# MCU.net
KiCad netlist of a schematic drawn in Altium Designer
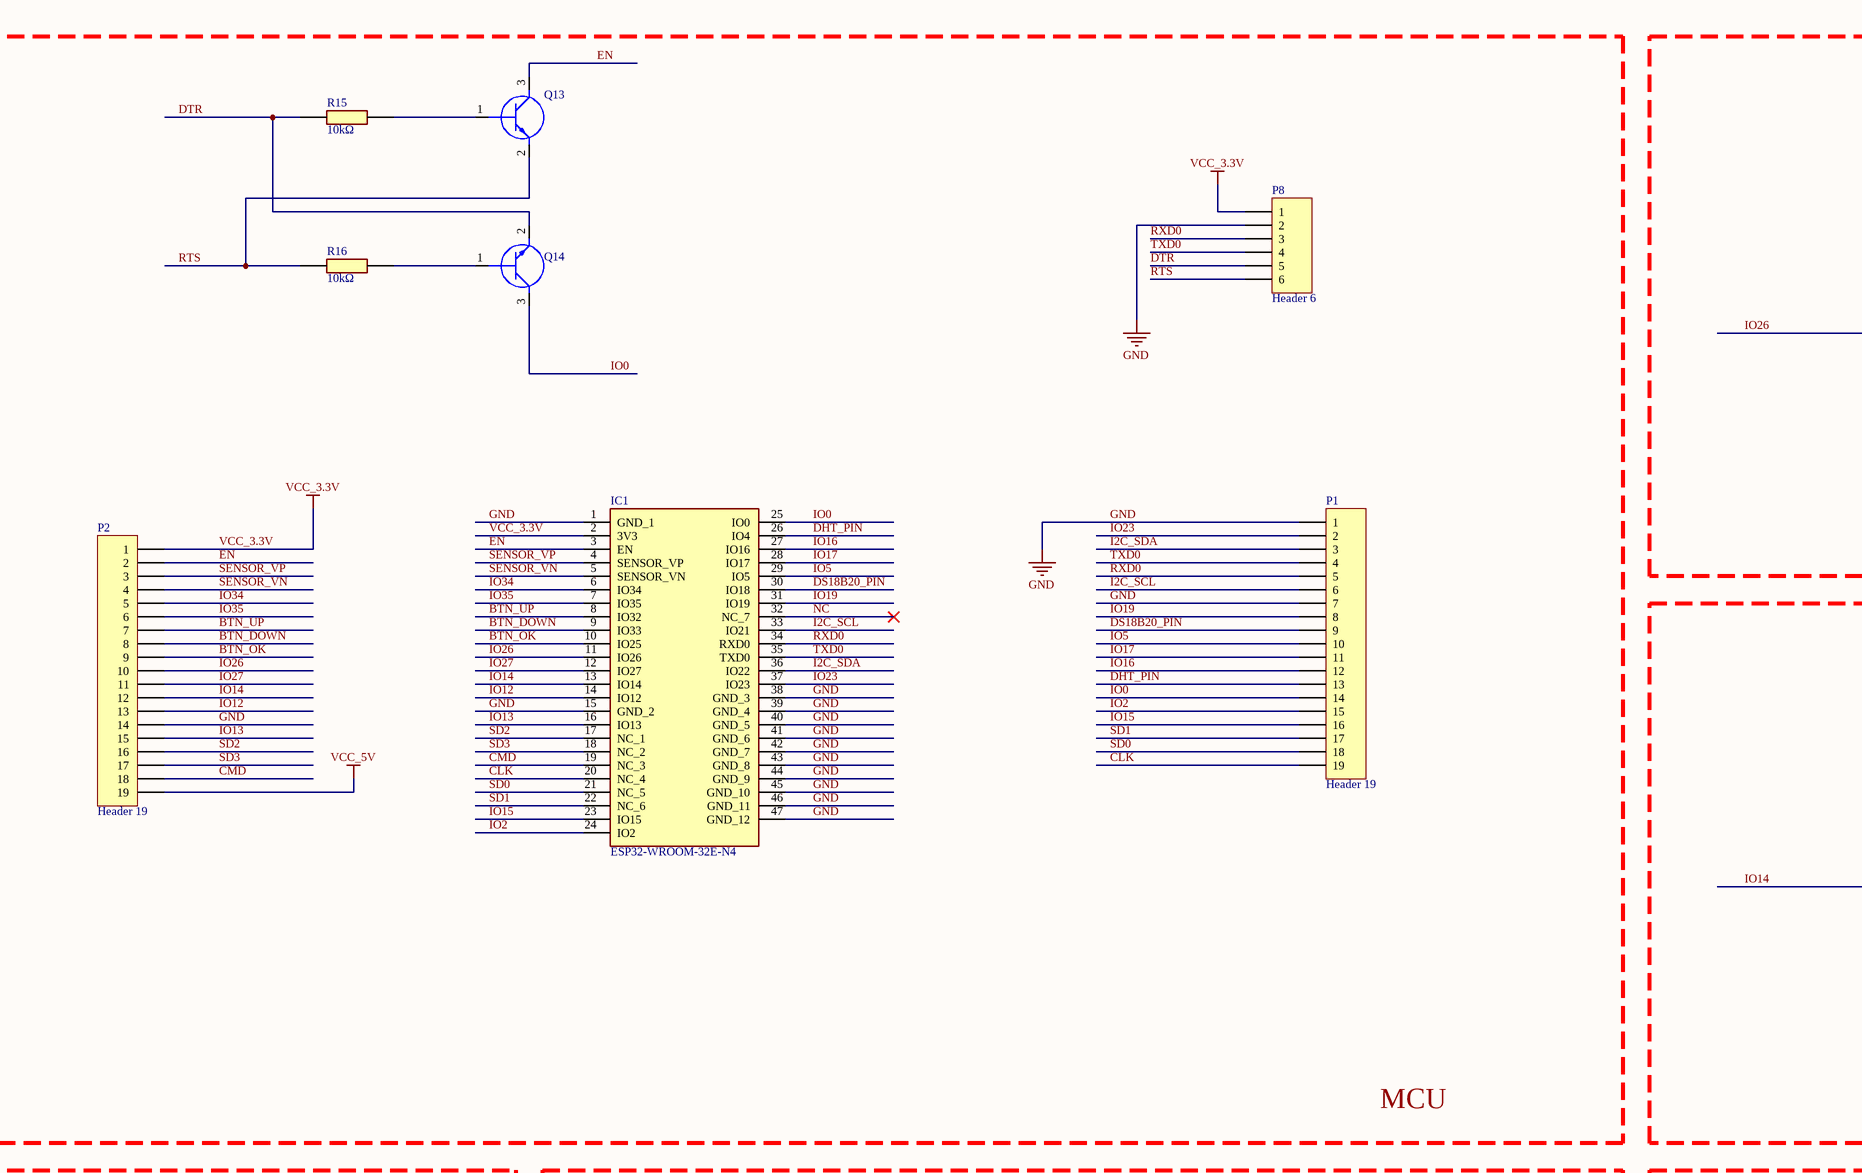
[diagram p0: MCU.SchDoc, top left]
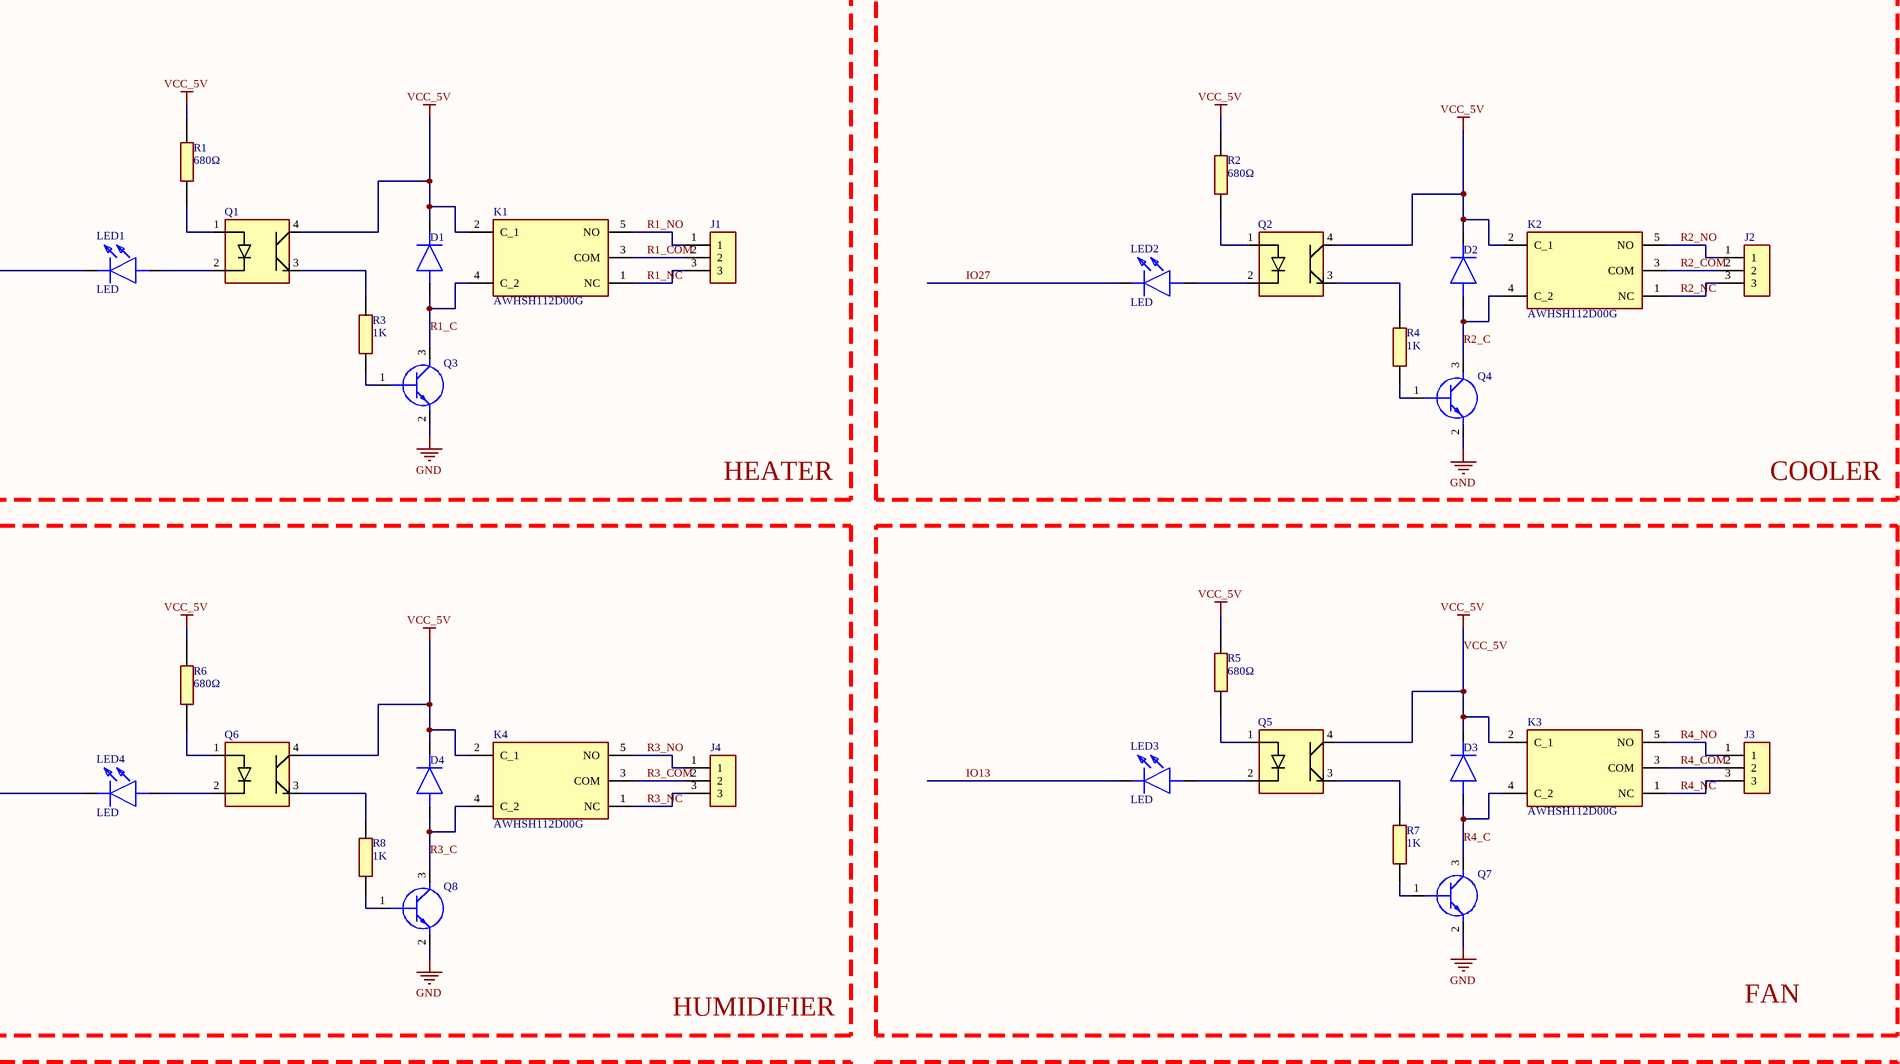
[diagram p1: MCU.SchDoc, top right]
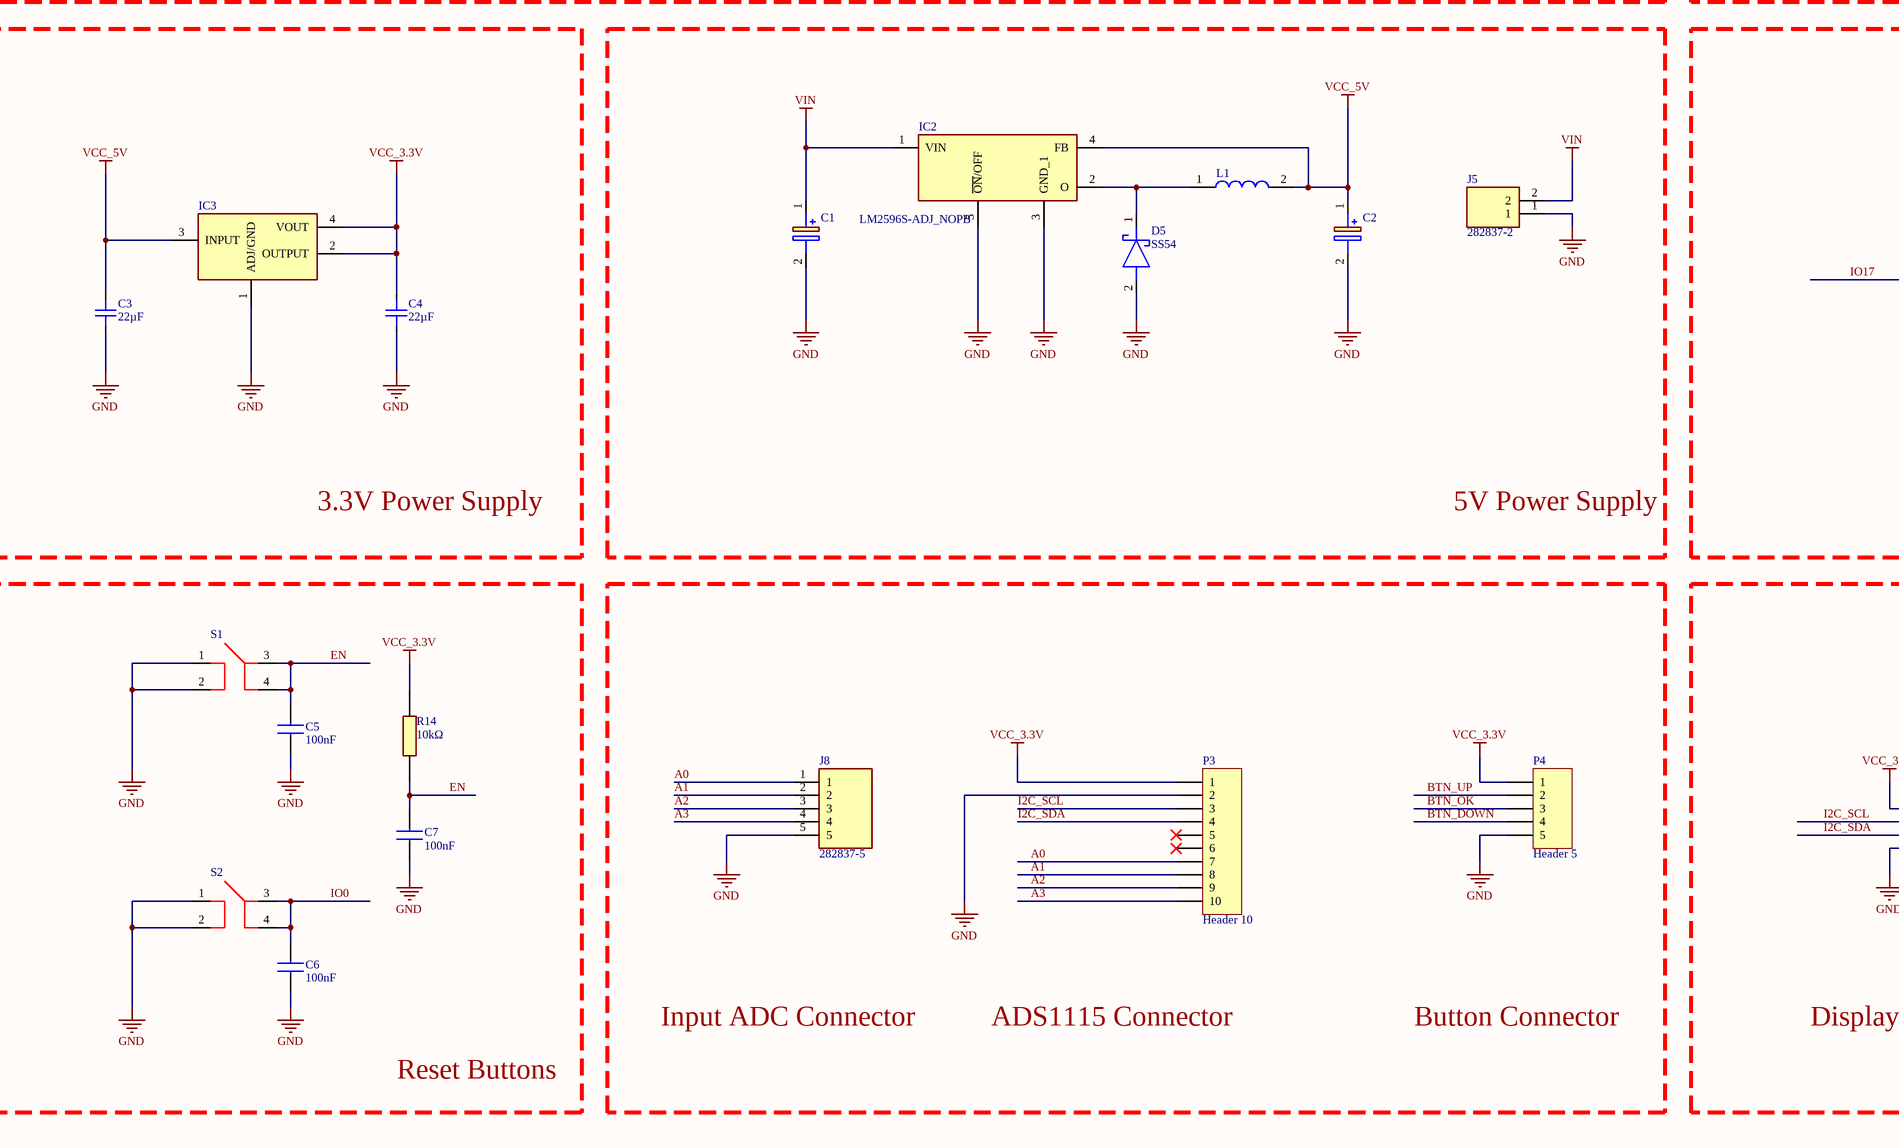
[diagram p2: MCU.SchDoc, bottom left]
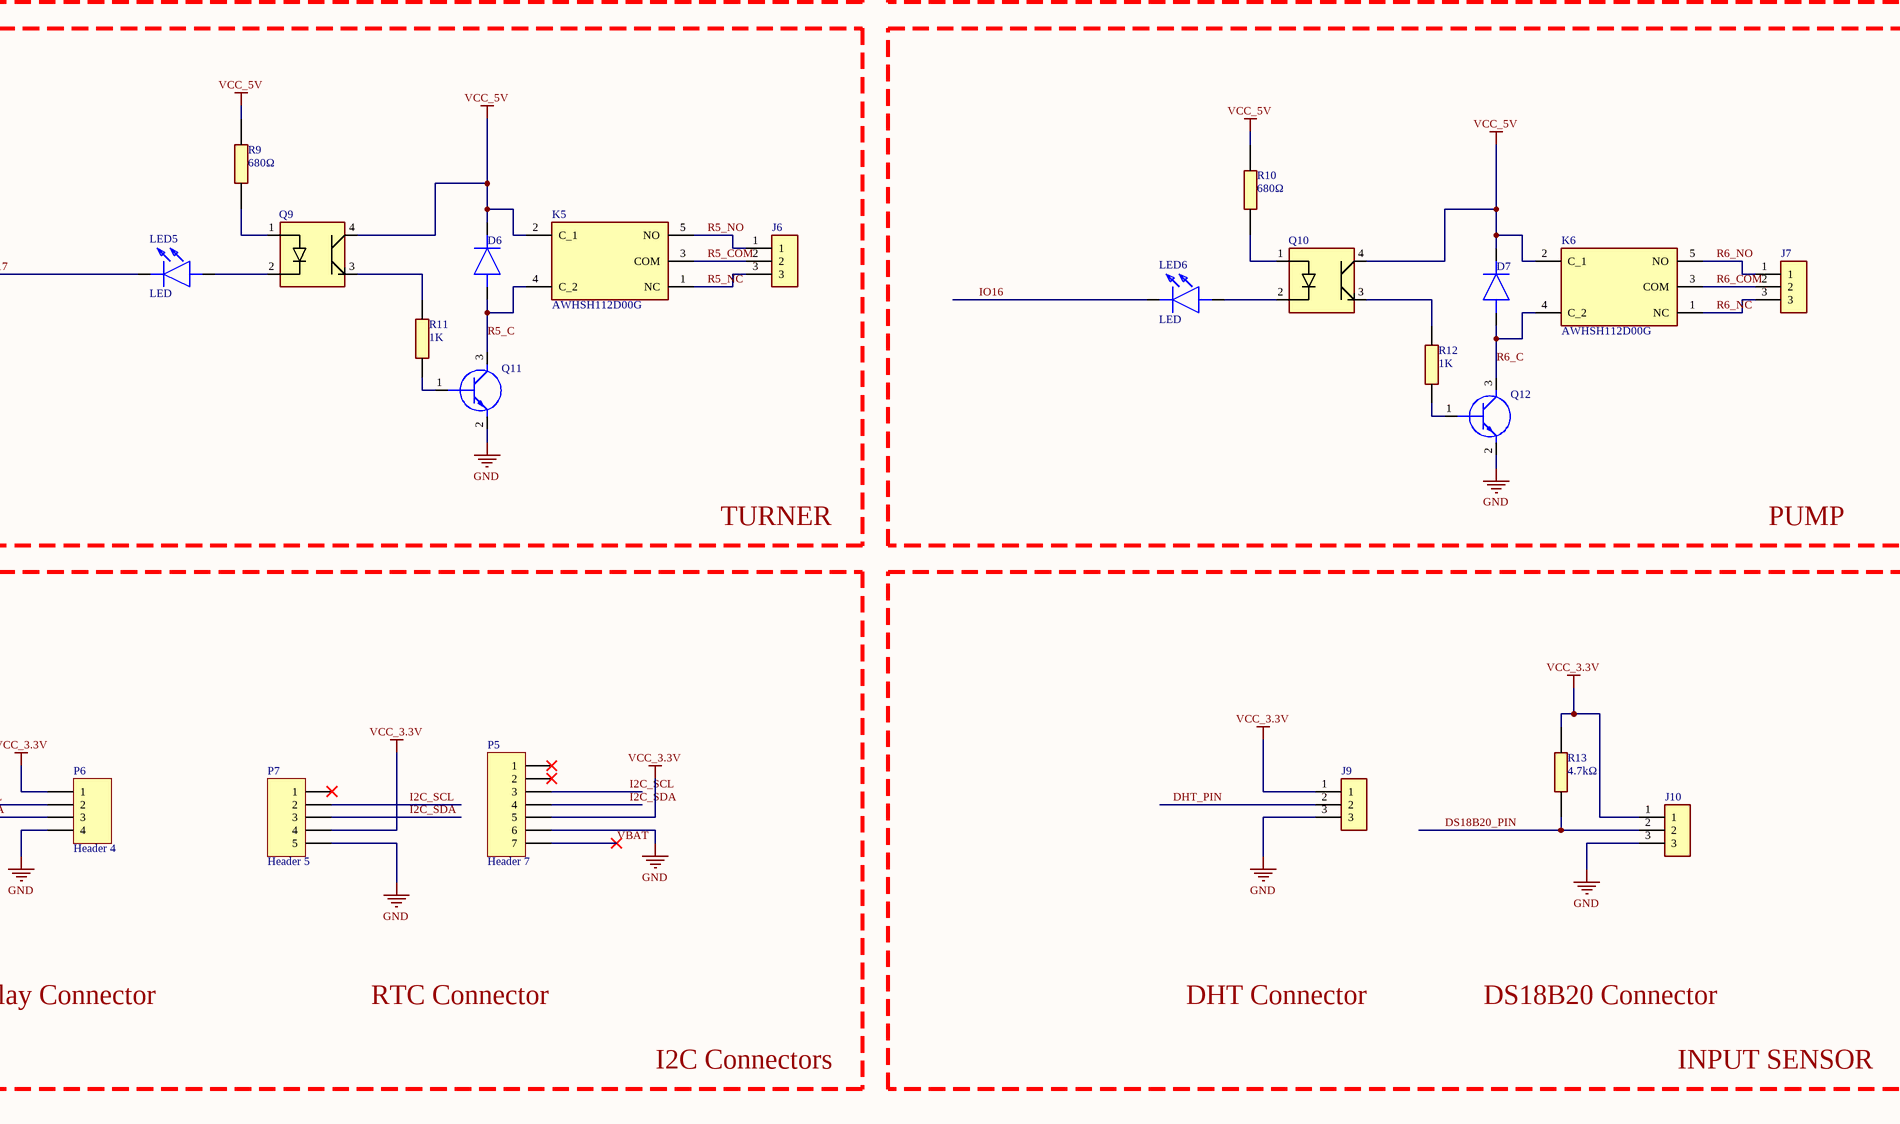
[diagram p3: MCU.SchDoc, bottom right]

(export (version "E")
  (design (tool "Eeschema 10.0.6"))
  (components
    (comp (ref "C1")
      (value "865060453007")
      (footprint "eggubator:CAPAE830X1050N")
      (description "Capacitor Polarised")
      (fields (field (name "MOUSER PART NUMBER") "710-865060453007"))
      (libsource (lib "*") (part "865060453007"))
    )
    (comp (ref "C2")
      (value "865060453007")
      (footprint "eggubator:CAPAE830X1050N")
      (description "Capacitor Polarised")
      (fields (field (name "MOUSER PART NUMBER") "710-865060453007"))
      (libsource (lib "*") (part "865060453007"))
    )
    (comp (ref "C3")
      (value "22µF")
      (footprint "C0805")
      (description "16V 22uF X5R ±20% 0805 Multilayer Ceramic Capacitors MLCC - SMD/SMT ROHS")
      (fields
        (field (name "MANUFACTURER") "Yageo Group")
        (field (name "MANUFACTURER PART NUMBER") "CC0805MKX5R7BB226")
      )
      (libsource (lib "eggubator") (part "CC0805MKX5R7BB226"))
    )
    (comp (ref "C4")
      (value "22µF")
      (footprint "C0805")
      (description "16V 22uF X5R ±20% 0805 Multilayer Ceramic Capacitors MLCC - SMD/SMT ROHS")
      (fields
        (field (name "MANUFACTURER") "Yageo Group")
        (field (name "MANUFACTURER PART NUMBER") "CC0805MKX5R7BB226")
      )
      (libsource (lib "eggubator") (part "CC0805MKX5R7BB226"))
    )
    (comp (ref "C5")
      (value "100nF")
      (footprint "C0805")
      (description "50V 100nF X7R ±10% 0805 Multilayer Ceramic Capacitors MLCC - SMD/SMT ROHS")
      (fields
        (field (name "MANUFACTURER") "Yageo Group")
        (field (name "MANUFACTURER PART NUMBER") "C0805C104K5RACTU")
      )
      (libsource (lib "eggubator") (part "C0805C104K5RACTU"))
    )
    (comp (ref "C6")
      (value "100nF")
      (footprint "C0805")
      (description "50V 100nF X7R ±10% 0805 Multilayer Ceramic Capacitors MLCC - SMD/SMT ROHS")
      (fields
        (field (name "MANUFACTURER") "Yageo Group")
        (field (name "MANUFACTURER PART NUMBER") "C0805C104K5RACTU")
      )
      (libsource (lib "eggubator") (part "C0805C104K5RACTU"))
    )
    (comp (ref "C7")
      (value "100nF")
      (footprint "C0805")
      (description "50V 100nF X7R ±10% 0805 Multilayer Ceramic Capacitors MLCC - SMD/SMT ROHS")
      (fields
        (field (name "MANUFACTURER") "Yageo Group")
        (field (name "MANUFACTURER PART NUMBER") "C0805C104K5RACTU")
      )
      (libsource (lib "eggubator") (part "C0805C104K5RACTU"))
    )
    (comp (ref "D1")
      (value "1N4007FLTR")
      (footprint "eggubator:SODFL3718X140N")
      (description "Diode")
      (libsource (lib "eggubator") (part "1N4007FLTR"))
    )
    (comp (ref "D2")
      (value "1N4007FLTR")
      (footprint "eggubator:SODFL3718X140N")
      (description "Diode")
      (libsource (lib "eggubator") (part "1N4007FLTR"))
    )
    (comp (ref "D3")
      (value "1N4007FLTR")
      (footprint "eggubator:SODFL3718X140N")
      (description "Diode")
      (libsource (lib "eggubator") (part "1N4007FLTR"))
    )
    (comp (ref "D4")
      (value "1N4007FLTR")
      (footprint "eggubator:SODFL3718X140N")
      (description "Diode")
      (libsource (lib "eggubator") (part "1N4007FLTR"))
    )
    (comp (ref "D5")
      (value "SS54")
      (footprint "eggubator:DIOM5026X262N")
      (description "Schottky Diode")
      (libsource (lib "*") (part "SS54"))
    )
    (comp (ref "D6")
      (value "1N4007FLTR")
      (footprint "eggubator:SODFL3718X140N")
      (description "Diode")
      (libsource (lib "eggubator") (part "1N4007FLTR"))
    )
    (comp (ref "D7")
      (value "1N4007FLTR")
      (footprint "eggubator:SODFL3718X140N")
      (description "Diode")
      (libsource (lib "eggubator") (part "1N4007FLTR"))
    )
    (comp (ref "IC1")
      (value "ESP32-WROOM-32E-N4")
      (footprint "eggubator:ESP32WROOM32EN4")
      (description "Integrated Circuit")
      (fields (field (name "MOUSER PART NUMBER") "356-ESP32WRM32E132PH"))
      (libsource (lib "*") (part "ESP32-WROOM-32E-N4"))
    )
    (comp (ref "IC2")
      (value "LM2596S-ADJ_NOPB")
      (footprint "eggubator:LM2596SXADJ")
      (description "Integrated Circuit")
      (fields
        (field (name "MANUFACTURER_PART_NUMBER") "LM2596S-ADJ/NOPB")
        (field (name "MOUSER PART NUMBER") "926-LM2596S-ADJ/NOPB")
      )
      (libsource (lib "eggubator") (part "LM2596S-ADJ_NOPB"))
    )
    (comp (ref "IC3")
      (value "LM1117IMPX3.3_NOPB")
      (footprint "eggubator:SOT230P700X180-4N")
      (description "Integrated Circuit")
      (fields (field (name "MANUFACTURER_PART_NUMBER") "LM1117IMPX3.3/NOPB"))
      (libsource (lib "eggubator") (part "LM1117IMPX3.3_NOPB"))
    )
    (comp (ref "J1")
      (value "691137710003")
      (footprint "eggubator:691137710003")
      (description "Connector")
      (fields (field (name "MOUSER PART NUMBER") "710-691137710003"))
      (libsource (lib "eggubator") (part "691137710003"))
    )
    (comp (ref "J2")
      (value "691137710003")
      (footprint "eggubator:691137710003")
      (description "Connector")
      (fields (field (name "MOUSER PART NUMBER") "710-691137710003"))
      (libsource (lib "eggubator") (part "691137710003"))
    )
    (comp (ref "J3")
      (value "691137710003")
      (footprint "eggubator:691137710003")
      (description "Connector")
      (fields (field (name "MOUSER PART NUMBER") "710-691137710003"))
      (libsource (lib "eggubator") (part "691137710003"))
    )
    (comp (ref "J4")
      (value "691137710003")
      (footprint "eggubator:691137710003")
      (description "Connector")
      (fields (field (name "MOUSER PART NUMBER") "710-691137710003"))
      (libsource (lib "eggubator") (part "691137710003"))
    )
    (comp (ref "J5")
      (value "282837-2")
      (footprint "eggubator:2828372")
      (description "Connector")
      (fields (field (name "MOUSER PART NUMBER") "571-2828372"))
      (libsource (lib "*") (part "282837-2"))
    )
    (comp (ref "J6")
      (value "691137710003")
      (footprint "eggubator:691137710003")
      (description "Connector")
      (fields (field (name "MOUSER PART NUMBER") "710-691137710003"))
      (libsource (lib "eggubator") (part "691137710003"))
    )
    (comp (ref "J7")
      (value "691137710003")
      (footprint "eggubator:691137710003")
      (description "Connector")
      (fields (field (name "MOUSER PART NUMBER") "710-691137710003"))
      (libsource (lib "eggubator") (part "691137710003"))
    )
    (comp (ref "J8")
      (value "282837-5")
      (footprint "eggubator:2828375")
      (description "Connector")
      (fields (field (name "MOUSER PART NUMBER") "571-2828375"))
      (libsource (lib "*") (part "282837-5"))
    )
    (comp (ref "J9")
      (value "691137710003")
      (footprint "eggubator:691137710003")
      (description "Connector")
      (fields (field (name "MOUSER PART NUMBER") "710-691137710003"))
      (libsource (lib "eggubator") (part "691137710003"))
    )
    (comp (ref "J10")
      (value "691137710003")
      (footprint "eggubator:691137710003")
      (description "Connector")
      (fields (field (name "MOUSER PART NUMBER") "710-691137710003"))
      (libsource (lib "eggubator") (part "691137710003"))
    )
    (comp (ref "K1")
      (value "AWHSH112D00G")
      (footprint "eggubator:AWHSH112D00G")
      (description "Relay or Contactor")
      (fields (field (name "MOUSER PART NUMBER") "523-AWHSH112D00G"))
      (libsource (lib "eggubator") (part "AWHSH112D00G"))
    )
    (comp (ref "K2")
      (value "AWHSH112D00G")
      (footprint "eggubator:AWHSH112D00G")
      (description "Relay or Contactor")
      (fields (field (name "MOUSER PART NUMBER") "523-AWHSH112D00G"))
      (libsource (lib "eggubator") (part "AWHSH112D00G"))
    )
    (comp (ref "K3")
      (value "AWHSH112D00G")
      (footprint "eggubator:AWHSH112D00G")
      (description "Relay or Contactor")
      (fields (field (name "MOUSER PART NUMBER") "523-AWHSH112D00G"))
      (libsource (lib "eggubator") (part "AWHSH112D00G"))
    )
    (comp (ref "K4")
      (value "AWHSH112D00G")
      (footprint "eggubator:AWHSH112D00G")
      (description "Relay or Contactor")
      (fields (field (name "MOUSER PART NUMBER") "523-AWHSH112D00G"))
      (libsource (lib "eggubator") (part "AWHSH112D00G"))
    )
    (comp (ref "K5")
      (value "AWHSH112D00G")
      (footprint "eggubator:AWHSH112D00G")
      (description "Relay or Contactor")
      (fields (field (name "MOUSER PART NUMBER") "523-AWHSH112D00G"))
      (libsource (lib "eggubator") (part "AWHSH112D00G"))
    )
    (comp (ref "K6")
      (value "AWHSH112D00G")
      (footprint "eggubator:AWHSH112D00G")
      (description "Relay or Contactor")
      (fields (field (name "MOUSER PART NUMBER") "523-AWHSH112D00G"))
      (libsource (lib "eggubator") (part "AWHSH112D00G"))
    )
    (comp (ref "L1")
      (value "CDRH104RNP-331NC")
      (footprint "eggubator:CDRH104RNP331NC")
      (description "Inductor")
      (fields (field (name "MOUSER PART NUMBER") "851-CDRH104RNP-331NC"))
      (libsource (lib "*") (part "CDRH104RNP-331NC"))
    )
    (comp (ref "LED1")
      (value "LED")
      (footprint "eggubator:XZMDK54W4")
      (description "Single Color LED, Red, Water Clear, 1.3mm")
      (fields (field (name "MANUFACTURER_PART_NUMBER") "XZMDK54W-4") (field (name "MANUFACTURER") "SunLED"))
      (libsource (lib "eggubator") (part "XZMDK54W-4"))
    )
    (comp (ref "LED2")
      (value "LED")
      (footprint "eggubator:XZMDK54W4")
      (description "Single Color LED, Red, Water Clear, 1.3mm")
      (fields (field (name "MANUFACTURER_PART_NUMBER") "XZMDK54W-4") (field (name "MANUFACTURER") "SunLED"))
      (libsource (lib "eggubator") (part "XZMDK54W-4"))
    )
    (comp (ref "LED3")
      (value "LED")
      (footprint "eggubator:XZMDK54W4")
      (description "Single Color LED, Red, Water Clear, 1.3mm")
      (fields (field (name "MANUFACTURER_PART_NUMBER") "XZMDK54W-4") (field (name "MANUFACTURER") "SunLED"))
      (libsource (lib "eggubator") (part "XZMDK54W-4"))
    )
    (comp (ref "LED4")
      (value "LED")
      (footprint "eggubator:XZMDK54W4")
      (description "Single Color LED, Red, Water Clear, 1.3mm")
      (fields (field (name "MANUFACTURER_PART_NUMBER") "XZMDK54W-4") (field (name "MANUFACTURER") "SunLED"))
      (libsource (lib "eggubator") (part "XZMDK54W-4"))
    )
    (comp (ref "LED5")
      (value "LED")
      (footprint "eggubator:XZMDK54W4")
      (description "Single Color LED, Red, Water Clear, 1.3mm")
      (fields (field (name "MANUFACTURER_PART_NUMBER") "XZMDK54W-4") (field (name "MANUFACTURER") "SunLED"))
      (libsource (lib "eggubator") (part "XZMDK54W-4"))
    )
    (comp (ref "LED6")
      (value "LED")
      (footprint "eggubator:XZMDK54W4")
      (description "Single Color LED, Red, Water Clear, 1.3mm")
      (fields (field (name "MANUFACTURER_PART_NUMBER") "XZMDK54W-4") (field (name "MANUFACTURER") "SunLED"))
      (libsource (lib "eggubator") (part "XZMDK54W-4"))
    )
    (comp (ref "P1")
      (value "Header 19")
      (footprint "HDR1X19")
      (description "Header, 19-Pin")
      (fields (field (name "PUBLISHER") "Altium Limited"))
      (libsource (lib "Miscellaneous Connectors") (part "Header 19"))
    )
    (comp (ref "P2")
      (value "Header 19")
      (footprint "HDR1X19")
      (description "Header, 19-Pin")
      (fields (field (name "PUBLISHER") "Altium Limited"))
      (libsource (lib "") (part "Header 19_1"))
    )
    (comp (ref "P3")
      (value "Header 10")
      (footprint "HDR1X10")
      (description "Header, 10-Pin")
      (fields (field (name "PUBLISHER") "Altium Limited"))
      (libsource (lib "Miscellaneous Connectors") (part "Header 10"))
    )
    (comp (ref "P4")
      (value "Header 5")
      (footprint "HDR1X5")
      (description "Header, 5-Pin")
      (fields (field (name "PUBLISHER") "Altium Limited"))
      (libsource (lib "") (part "Header 5_1"))
    )
    (comp (ref "P5")
      (value "Header 7")
      (footprint "HDR1X7")
      (description "Header, 7-Pin")
      (fields (field (name "PUBLISHER") "Altium Limited"))
      (libsource (lib "Miscellaneous Connectors") (part "Header 7"))
    )
    (comp (ref "P6")
      (value "Header 4")
      (footprint "HDR1X4")
      (description "Header, 4-Pin")
      (fields (field (name "PUBLISHER") "Altium Limited"))
      (libsource (lib "Miscellaneous Connectors") (part "Header 4"))
    )
    (comp (ref "P7")
      (value "Header 5")
      (footprint "HDR1X5")
      (description "Header, 5-Pin")
      (fields (field (name "PUBLISHER") "Altium Limited"))
      (libsource (lib "Miscellaneous Connectors") (part "Header 5"))
    )
    (comp (ref "P8")
      (value "Header 6")
      (footprint "HDR1X6")
      (description "Header, 6-Pin")
      (fields (field (name "PUBLISHER") "Altium Limited"))
      (libsource (lib "Miscellaneous Connectors") (part "Header 6"))
    )
    (comp (ref "Q1")
      (value "APC-817C1-SL")
      (footprint "eggubator:APC817C1SL")
      (description "Phototransistor")
      (fields (field (name "MOUSER PART NUMBER") "442-APC817C1SL"))
      (libsource (lib "eggubator") (part "APC-817C1-SL"))
    )
    (comp (ref "Q2")
      (value "APC-817C1-SL")
      (footprint "eggubator:APC817C1SL")
      (description "Phototransistor")
      (fields (field (name "MOUSER PART NUMBER") "442-APC817C1SL"))
      (libsource (lib "eggubator") (part "APC-817C1-SL"))
    )
    (comp (ref "Q3")
      (value "MMBT2222A-G")
      (footprint "eggubator:SOT95P240X115-3N")
      (description "Transistor BJT NPN")
      (fields (field (name "MOUSER PART NUMBER") "750-MMBT2222A-G"))
      (libsource (lib "*") (part "MMBT2222A-G"))
    )
    (comp (ref "Q4")
      (value "MMBT2222A-G")
      (footprint "eggubator:SOT95P240X115-3N")
      (description "Transistor BJT NPN")
      (fields (field (name "MOUSER PART NUMBER") "750-MMBT2222A-G"))
      (libsource (lib "*") (part "MMBT2222A-G"))
    )
    (comp (ref "Q5")
      (value "APC-817C1-SL")
      (footprint "eggubator:APC817C1SL")
      (description "Phototransistor")
      (fields (field (name "MOUSER PART NUMBER") "442-APC817C1SL"))
      (libsource (lib "eggubator") (part "APC-817C1-SL"))
    )
    (comp (ref "Q6")
      (value "APC-817C1-SL")
      (footprint "eggubator:APC817C1SL")
      (description "Phototransistor")
      (fields (field (name "MOUSER PART NUMBER") "442-APC817C1SL"))
      (libsource (lib "eggubator") (part "APC-817C1-SL"))
    )
    (comp (ref "Q7")
      (value "MMBT2222A-G")
      (footprint "eggubator:SOT95P240X115-3N")
      (description "Transistor BJT NPN")
      (fields (field (name "MOUSER PART NUMBER") "750-MMBT2222A-G"))
      (libsource (lib "*") (part "MMBT2222A-G"))
    )
    (comp (ref "Q8")
      (value "MMBT2222A-G")
      (footprint "eggubator:SOT95P240X115-3N")
      (description "Transistor BJT NPN")
      (fields (field (name "MOUSER PART NUMBER") "750-MMBT2222A-G"))
      (libsource (lib "*") (part "MMBT2222A-G"))
    )
    (comp (ref "Q9")
      (value "APC-817C1-SL")
      (footprint "eggubator:APC817C1SL")
      (description "Phototransistor")
      (fields (field (name "MOUSER PART NUMBER") "442-APC817C1SL"))
      (libsource (lib "eggubator") (part "APC-817C1-SL"))
    )
    (comp (ref "Q10")
      (value "APC-817C1-SL")
      (footprint "eggubator:APC817C1SL")
      (description "Phototransistor")
      (fields (field (name "MOUSER PART NUMBER") "442-APC817C1SL"))
      (libsource (lib "eggubator") (part "APC-817C1-SL"))
    )
    (comp (ref "Q11")
      (value "MMBT2222A-G")
      (footprint "eggubator:SOT95P240X115-3N")
      (description "Transistor BJT NPN")
      (fields (field (name "MOUSER PART NUMBER") "750-MMBT2222A-G"))
      (libsource (lib "*") (part "MMBT2222A-G"))
    )
    (comp (ref "Q12")
      (value "MMBT2222A-G")
      (footprint "eggubator:SOT95P240X115-3N")
      (description "Transistor BJT NPN")
      (fields (field (name "MOUSER PART NUMBER") "750-MMBT2222A-G"))
      (libsource (lib "*") (part "MMBT2222A-G"))
    )
    (comp (ref "Q13")
      (value "MMBT2222A-G")
      (footprint "eggubator:SOT95P240X115-3N")
      (description "Transistor BJT NPN")
      (fields (field (name "MOUSER PART NUMBER") "750-MMBT2222A-G"))
      (libsource (lib "*") (part "MMBT2222A-G"))
    )
    (comp (ref "Q14")
      (value "MMBT2222A-G")
      (footprint "eggubator:SOT95P240X115-3N")
      (description "Transistor BJT NPN")
      (fields (field (name "MOUSER PART NUMBER") "750-MMBT2222A-G"))
      (libsource (lib "*") (part "MMBT2222A-G"))
    )
    (comp (ref "R1")
      (value "680Ω")
      (footprint "RES 0805_2012 RF")
      (description "125mW Thin Film Resistor ±50ppm/℃ ±1% 680Ω 0805 Chip Resistor - Surface Mount ROHS")
      (fields
        (field (name "MANUFACTURER") "Yageo Group")
        (field (name "MANUFACTURER PART NUMBER") "RT0805FRE07680RL")
      )
      (libsource (lib "eggubator") (part "RT0805FRE07680RL"))
    )
    (comp (ref "R2")
      (value "680Ω")
      (footprint "RES 0805_2012 RF")
      (description "125mW Thin Film Resistor ±50ppm/℃ ±1% 680Ω 0805 Chip Resistor - Surface Mount ROHS")
      (fields
        (field (name "MANUFACTURER") "Yageo Group")
        (field (name "MANUFACTURER PART NUMBER") "RT0805FRE07680RL")
      )
      (libsource (lib "eggubator") (part "RT0805FRE07680RL"))
    )
    (comp (ref "R3")
      (value "1K")
      (footprint "eggubator:RESC2012X60N")
      (description "Resistor")
      (fields
        (field (name "MANUFACTURER_PART_NUMBER") "AT0805DRD071KL")
        (field (name "MOUSER PART NUMBER") "603-AT0805DRD071KL")
      )
      (libsource (lib "eggubator") (part "AT0805DRD071KL"))
    )
    (comp (ref "R4")
      (value "1K")
      (footprint "eggubator:RESC2012X60N")
      (description "Resistor")
      (fields
        (field (name "MANUFACTURER_PART_NUMBER") "AT0805DRD071KL")
        (field (name "MOUSER PART NUMBER") "603-AT0805DRD071KL")
      )
      (libsource (lib "eggubator") (part "AT0805DRD071KL"))
    )
    (comp (ref "R5")
      (value "680Ω")
      (footprint "RES 0805_2012 RF")
      (description "125mW Thin Film Resistor ±50ppm/℃ ±1% 680Ω 0805 Chip Resistor - Surface Mount ROHS")
      (fields
        (field (name "MANUFACTURER") "Yageo Group")
        (field (name "MANUFACTURER PART NUMBER") "RT0805FRE07680RL")
      )
      (libsource (lib "eggubator") (part "RT0805FRE07680RL"))
    )
    (comp (ref "R6")
      (value "680Ω")
      (footprint "RES 0805_2012 RF")
      (description "125mW Thin Film Resistor ±50ppm/℃ ±1% 680Ω 0805 Chip Resistor - Surface Mount ROHS")
      (fields
        (field (name "MANUFACTURER") "Yageo Group")
        (field (name "MANUFACTURER PART NUMBER") "RT0805FRE07680RL")
      )
      (libsource (lib "eggubator") (part "RT0805FRE07680RL"))
    )
    (comp (ref "R7")
      (value "1K")
      (footprint "eggubator:RESC2012X60N")
      (description "Resistor")
      (fields
        (field (name "MANUFACTURER_PART_NUMBER") "AT0805DRD071KL")
        (field (name "MOUSER PART NUMBER") "603-AT0805DRD071KL")
      )
      (libsource (lib "eggubator") (part "AT0805DRD071KL"))
    )
    (comp (ref "R8")
      (value "1K")
      (footprint "eggubator:RESC2012X60N")
      (description "Resistor")
      (fields
        (field (name "MANUFACTURER_PART_NUMBER") "AT0805DRD071KL")
        (field (name "MOUSER PART NUMBER") "603-AT0805DRD071KL")
      )
      (libsource (lib "eggubator") (part "AT0805DRD071KL"))
    )
    (comp (ref "R9")
      (value "680Ω")
      (footprint "RES 0805_2012 RF")
      (description "125mW Thin Film Resistor ±50ppm/℃ ±1% 680Ω 0805 Chip Resistor - Surface Mount ROHS")
      (fields
        (field (name "MANUFACTURER") "Yageo Group")
        (field (name "MANUFACTURER PART NUMBER") "RT0805FRE07680RL")
      )
      (libsource (lib "eggubator") (part "RT0805FRE07680RL"))
    )
    (comp (ref "R10")
      (value "680Ω")
      (footprint "RES 0805_2012 RF")
      (description "125mW Thin Film Resistor ±50ppm/℃ ±1% 680Ω 0805 Chip Resistor - Surface Mount ROHS")
      (fields
        (field (name "MANUFACTURER") "Yageo Group")
        (field (name "MANUFACTURER PART NUMBER") "RT0805FRE07680RL")
      )
      (libsource (lib "eggubator") (part "RT0805FRE07680RL"))
    )
    (comp (ref "R11")
      (value "1K")
      (footprint "eggubator:RESC2012X60N")
      (description "Resistor")
      (fields
        (field (name "MANUFACTURER_PART_NUMBER") "AT0805DRD071KL")
        (field (name "MOUSER PART NUMBER") "603-AT0805DRD071KL")
      )
      (libsource (lib "eggubator") (part "AT0805DRD071KL"))
    )
    (comp (ref "R12")
      (value "1K")
      (footprint "eggubator:RESC2012X60N")
      (description "Resistor")
      (fields
        (field (name "MANUFACTURER_PART_NUMBER") "AT0805DRD071KL")
        (field (name "MOUSER PART NUMBER") "603-AT0805DRD071KL")
      )
      (libsource (lib "eggubator") (part "AT0805DRD071KL"))
    )
    (comp (ref "R13")
      (value "4.7kΩ")
      (footprint "RES 0805_2012 RF")
      (description "Res Thick Film 0805 4.7K Ohm 1% 0.125W(1/8W) ±100ppm/C Sulfur Resistant Pad SMD Automotive T/R")
      (fields
        (field (name "MANUFACTURER") "Yageo Group")
        (field (name "MANUFACTURER PART NUMBER") "AF0805FR-074K7L")
      )
      (libsource (lib "eggubator") (part "AF0805FR-074K7L"))
    )
    (comp (ref "R14")
      (value "10kΩ")
      (footprint "eggubator:RESC2012X60N")
      (description "Res General Purpose Thick Film 0805 10k Ohm 1% 1/8W ±100ppm/°C Ceramic Paper T/R")
      (fields
        (field (name "MANUFACTURER_PART_NUMBER") "RC0805FR-0710KL")
        (field (name "MOUSER PART NUMBER") "603-RC0805FR-0710KL")
      )
      (libsource (lib "") (part "RC0805FR-0710KL_1"))
    )
    (comp (ref "R15")
      (value "10kΩ")
      (footprint "eggubator:RESC2012X60N")
      (description "Res General Purpose Thick Film 0805 10k Ohm 1% 1/8W ±100ppm/°C Ceramic Paper T/R")
      (fields
        (field (name "MANUFACTURER_PART_NUMBER") "RC0805FR-0710KL")
        (field (name "MOUSER PART NUMBER") "603-RC0805FR-0710KL")
      )
      (libsource (lib "eggubator") (part "RC0805FR-0710KL"))
    )
    (comp (ref "R16")
      (value "10kΩ")
      (footprint "eggubator:RESC2012X60N")
      (description "Res General Purpose Thick Film 0805 10k Ohm 1% 1/8W ±100ppm/°C Ceramic Paper T/R")
      (fields
        (field (name "MANUFACTURER_PART_NUMBER") "RC0805FR-0710KL")
        (field (name "MOUSER PART NUMBER") "603-RC0805FR-0710KL")
      )
      (libsource (lib "eggubator") (part "RC0805FR-0710KL"))
    )
    (comp (ref "S1")
      (value "TL1105AF160Q")
      (footprint "eggubator:TL1105AF160Q")
      (description "Switch")
      (fields (field (name "MOUSER PART NUMBER") "612-TL1105A"))
      (libsource (lib "eggubator") (part "TL1105AF160Q"))
    )
    (comp (ref "S2")
      (value "TL1105AF160Q")
      (footprint "eggubator:TL1105AF160Q")
      (description "Switch")
      (fields (field (name "MOUSER PART NUMBER") "612-TL1105A"))
      (libsource (lib "eggubator") (part "TL1105AF160Q"))
    )
  )
  (nets
    (net (code "1") (name "/A0") (class "Default")
      (node (ref "J8") (pin "1") (pinfunction "1_1") (pintype "passive"))
      (node (ref "P3") (pin "7") (pinfunction "7_7") (pintype "passive"))
    )
    (net (code "2") (name "/A1") (class "Default")
      (node (ref "J8") (pin "2") (pinfunction "2_2") (pintype "passive"))
      (node (ref "P3") (pin "8") (pinfunction "8_8") (pintype "passive"))
    )
    (net (code "3") (name "/A2") (class "Default")
      (node (ref "J8") (pin "3") (pinfunction "3_3") (pintype "passive"))
      (node (ref "P3") (pin "9") (pinfunction "9_9") (pintype "passive"))
    )
    (net (code "4") (name "/A3") (class "Default")
      (node (ref "J8") (pin "4") (pinfunction "4_4") (pintype "passive"))
      (node (ref "P3") (pin "10") (pinfunction "10_10") (pintype "passive"))
    )
    (net (code "5") (name "/BTN_DOWN") (class "Default")
      (node (ref "IC1") (pin "9") (pinfunction "IO33_9") (pintype "passive"))
      (node (ref "P2") (pin "8") (pinfunction "8_8") (pintype "passive"))
      (node (ref "P4") (pin "4") (pinfunction "4_4") (pintype "passive"))
    )
    (net (code "6") (name "/BTN_OK") (class "Default")
      (node (ref "IC1") (pin "10") (pinfunction "IO25_10") (pintype "passive"))
      (node (ref "P2") (pin "9") (pinfunction "9_9") (pintype "passive"))
      (node (ref "P4") (pin "3") (pinfunction "3_3") (pintype "passive"))
    )
    (net (code "7") (name "/BTN_UP") (class "Default")
      (node (ref "IC1") (pin "8") (pinfunction "IO32_8") (pintype "passive"))
      (node (ref "P2") (pin "7") (pinfunction "7_7") (pintype "passive"))
      (node (ref "P4") (pin "2") (pinfunction "2_2") (pintype "passive"))
    )
    (net (code "8") (name "/CLK") (class "Default")
      (node (ref "IC1") (pin "20") (pinfunction "NC_4_20") (pintype "passive"))
      (node (ref "P1") (pin "19") (pinfunction "19_19") (pintype "passive"))
    )
    (net (code "9") (name "/CMD") (class "Default")
      (node (ref "IC1") (pin "19") (pinfunction "NC_3_19") (pintype "passive"))
      (node (ref "P2") (pin "18") (pinfunction "18_18") (pintype "passive"))
    )
    (net (code "10") (name "/DHT_PIN") (class "Default")
      (node (ref "IC1") (pin "26") (pinfunction "IO4_26") (pintype "passive"))
      (node (ref "J9") (pin "2") (pinfunction "2_2") (pintype "passive"))
      (node (ref "P1") (pin "13") (pinfunction "13_13") (pintype "passive"))
    )
    (net (code "11") (name "/DS18B20_PIN") (class "Default")
      (node (ref "IC1") (pin "30") (pinfunction "IO18_30") (pintype "passive"))
      (node (ref "J10") (pin "2") (pinfunction "2_2") (pintype "passive"))
      (node (ref "P1") (pin "9") (pinfunction "9_9") (pintype "passive"))
      (node (ref "R13") (pin "1") (pinfunction "1_1") (pintype "passive"))
    )
    (net (code "12") (name "/DTR") (class "Default")
      (node (ref "P8") (pin "5") (pinfunction "5_5") (pintype "passive"))
      (node (ref "Q14") (pin "2") (pinfunction "E_2") (pintype "passive"))
      (node (ref "R15") (pin "2") (pinfunction "2_2") (pintype "passive"))
    )
    (net (code "13") (name "/EN") (class "Default")
      (node (ref "C5") (pin "1") (pinfunction "1_1") (pintype "passive"))
      (node (ref "C7") (pin "1") (pinfunction "1_1") (pintype "passive"))
      (node (ref "IC1") (pin "3") (pinfunction "EN_3") (pintype "passive"))
      (node (ref "P2") (pin "2") (pinfunction "2_2") (pintype "passive"))
      (node (ref "Q13") (pin "3") (pinfunction "C_3") (pintype "passive"))
      (node (ref "R14") (pin "1") (pinfunction "1_1") (pintype "passive"))
      (node (ref "S1") (pin "3") (pinfunction "NO_1_3") (pintype "passive"))
      (node (ref "S1") (pin "4") (pinfunction "NO_2_4") (pintype "passive"))
    )
    (net (code "14") (name "/I2C_SCL") (class "Default")
      (node (ref "IC1") (pin "33") (pinfunction "IO21_33") (pintype "passive"))
      (node (ref "P1") (pin "6") (pinfunction "6_6") (pintype "passive"))
      (node (ref "P3") (pin "3") (pinfunction "3_3") (pintype "passive"))
      (node (ref "P5") (pin "3") (pinfunction "3_3") (pintype "passive"))
      (node (ref "P6") (pin "2") (pinfunction "2_2") (pintype "passive"))
      (node (ref "P7") (pin "2") (pinfunction "2_2") (pintype "passive"))
    )
    (net (code "15") (name "/I2C_SDA") (class "Default")
      (node (ref "IC1") (pin "36") (pinfunction "IO22_36") (pintype "passive"))
      (node (ref "P1") (pin "3") (pinfunction "3_3") (pintype "passive"))
      (node (ref "P3") (pin "4") (pinfunction "4_4") (pintype "passive"))
      (node (ref "P5") (pin "4") (pinfunction "4_4") (pintype "passive"))
      (node (ref "P6") (pin "3") (pinfunction "3_3") (pintype "passive"))
      (node (ref "P7") (pin "3") (pinfunction "3_3") (pintype "passive"))
    )
    (net (code "16") (name "/IO0") (class "Default")
      (node (ref "C6") (pin "1") (pinfunction "1_1") (pintype "passive"))
      (node (ref "IC1") (pin "25") (pinfunction "IO0_25") (pintype "passive"))
      (node (ref "P1") (pin "14") (pinfunction "14_14") (pintype "passive"))
      (node (ref "Q14") (pin "3") (pinfunction "C_3") (pintype "passive"))
      (node (ref "S2") (pin "3") (pinfunction "NO_1_3") (pintype "passive"))
      (node (ref "S2") (pin "4") (pinfunction "NO_2_4") (pintype "passive"))
    )
    (net (code "17") (name "/IO2") (class "Default")
      (node (ref "IC1") (pin "24") (pinfunction "IO2_24") (pintype "passive"))
      (node (ref "P1") (pin "15") (pinfunction "15_15") (pintype "passive"))
    )
    (net (code "18") (name "/IO5") (class "Default")
      (node (ref "IC1") (pin "29") (pinfunction "IO5_29") (pintype "passive"))
      (node (ref "P1") (pin "10") (pinfunction "10_10") (pintype "passive"))
    )
    (net (code "19") (name "/IO12") (class "Default")
      (node (ref "IC1") (pin "14") (pinfunction "IO12_14") (pintype "passive"))
      (node (ref "P2") (pin "13") (pinfunction "13_13") (pintype "passive"))
    )
    (net (code "20") (name "/IO13") (class "Default")
      (node (ref "IC1") (pin "16") (pinfunction "IO13_16") (pintype "passive"))
      (node (ref "LED3") (pin "1") (pinfunction "K_1") (pintype "passive"))
      (node (ref "P2") (pin "15") (pinfunction "15_15") (pintype "passive"))
    )
    (net (code "21") (name "/IO14") (class "Default")
      (node (ref "IC1") (pin "13") (pinfunction "IO14_13") (pintype "passive"))
      (node (ref "LED4") (pin "1") (pinfunction "K_1") (pintype "passive"))
      (node (ref "P2") (pin "12") (pinfunction "12_12") (pintype "passive"))
    )
    (net (code "22") (name "/IO15") (class "Default")
      (node (ref "IC1") (pin "23") (pinfunction "IO15_23") (pintype "passive"))
      (node (ref "P1") (pin "16") (pinfunction "16_16") (pintype "passive"))
    )
    (net (code "23") (name "/IO16") (class "Default")
      (node (ref "IC1") (pin "27") (pinfunction "IO16_27") (pintype "passive"))
      (node (ref "LED6") (pin "1") (pinfunction "K_1") (pintype "passive"))
      (node (ref "P1") (pin "12") (pinfunction "12_12") (pintype "passive"))
    )
    (net (code "24") (name "/IO17") (class "Default")
      (node (ref "IC1") (pin "28") (pinfunction "IO17_28") (pintype "passive"))
      (node (ref "LED5") (pin "1") (pinfunction "K_1") (pintype "passive"))
      (node (ref "P1") (pin "11") (pinfunction "11_11") (pintype "passive"))
    )
    (net (code "25") (name "/IO19") (class "Default")
      (node (ref "IC1") (pin "31") (pinfunction "IO19_31") (pintype "passive"))
      (node (ref "P1") (pin "8") (pinfunction "8_8") (pintype "passive"))
    )
    (net (code "26") (name "/IO23") (class "Default")
      (node (ref "IC1") (pin "37") (pinfunction "IO23_37") (pintype "passive"))
      (node (ref "P1") (pin "2") (pinfunction "2_2") (pintype "passive"))
    )
    (net (code "27") (name "/IO26") (class "Default")
      (node (ref "IC1") (pin "11") (pinfunction "IO26_11") (pintype "passive"))
      (node (ref "LED1") (pin "1") (pinfunction "K_1") (pintype "passive"))
      (node (ref "P2") (pin "10") (pinfunction "10_10") (pintype "passive"))
    )
    (net (code "28") (name "/IO27") (class "Default")
      (node (ref "IC1") (pin "12") (pinfunction "IO27_12") (pintype "passive"))
      (node (ref "LED2") (pin "1") (pinfunction "K_1") (pintype "passive"))
      (node (ref "P2") (pin "11") (pinfunction "11_11") (pintype "passive"))
    )
    (net (code "29") (name "/IO34") (class "Default")
      (node (ref "IC1") (pin "6") (pinfunction "IO34_6") (pintype "passive"))
      (node (ref "P2") (pin "5") (pinfunction "5_5") (pintype "passive"))
    )
    (net (code "30") (name "/IO35") (class "Default")
      (node (ref "IC1") (pin "7") (pinfunction "IO35_7") (pintype "passive"))
      (node (ref "P2") (pin "6") (pinfunction "6_6") (pintype "passive"))
    )
    (net (code "31") (name "/NC") (class "Default")
      (node (ref "IC1") (pin "32") (pinfunction "NC_7_32") (pintype "passive+no_connect"))
    )
    (net (code "32") (name "/R1_C") (class "Default")
      (node (ref "D1") (pin "2") (pinfunction "A_2") (pintype "passive"))
      (node (ref "K1") (pin "4") (pinfunction "C_2_4") (pintype "passive"))
      (node (ref "Q3") (pin "3") (pinfunction "C_3") (pintype "passive"))
    )
    (net (code "33") (name "/R1_COM") (class "Default")
      (node (ref "J1") (pin "2") (pinfunction "2_2") (pintype "passive"))
      (node (ref "K1") (pin "3") (pinfunction "COM_3") (pintype "passive"))
    )
    (net (code "34") (name "/R1_NC") (class "Default")
      (node (ref "J1") (pin "3") (pinfunction "3_3") (pintype "passive"))
      (node (ref "K1") (pin "1") (pinfunction "NC_1") (pintype "passive"))
    )
    (net (code "35") (name "/R1_NO") (class "Default")
      (node (ref "J1") (pin "1") (pinfunction "1_1") (pintype "passive"))
      (node (ref "K1") (pin "5") (pinfunction "NO_5") (pintype "passive"))
    )
    (net (code "36") (name "/R2_C") (class "Default")
      (node (ref "D2") (pin "2") (pinfunction "A_2") (pintype "passive"))
      (node (ref "K2") (pin "4") (pinfunction "C_2_4") (pintype "passive"))
      (node (ref "Q4") (pin "3") (pinfunction "C_3") (pintype "passive"))
    )
    (net (code "37") (name "/R2_COM") (class "Default")
      (node (ref "J2") (pin "2") (pinfunction "2_2") (pintype "passive"))
      (node (ref "K2") (pin "3") (pinfunction "COM_3") (pintype "passive"))
    )
    (net (code "38") (name "/R2_NC") (class "Default")
      (node (ref "J2") (pin "3") (pinfunction "3_3") (pintype "passive"))
      (node (ref "K2") (pin "1") (pinfunction "NC_1") (pintype "passive"))
    )
    (net (code "39") (name "/R2_NO") (class "Default")
      (node (ref "J2") (pin "1") (pinfunction "1_1") (pintype "passive"))
      (node (ref "K2") (pin "5") (pinfunction "NO_5") (pintype "passive"))
    )
    (net (code "40") (name "/R3_C") (class "Default")
      (node (ref "D4") (pin "2") (pinfunction "A_2") (pintype "passive"))
      (node (ref "K4") (pin "4") (pinfunction "C_2_4") (pintype "passive"))
      (node (ref "Q8") (pin "3") (pinfunction "C_3") (pintype "passive"))
    )
    (net (code "41") (name "/R3_COM") (class "Default")
      (node (ref "J4") (pin "2") (pinfunction "2_2") (pintype "passive"))
      (node (ref "K4") (pin "3") (pinfunction "COM_3") (pintype "passive"))
    )
    (net (code "42") (name "/R3_NC") (class "Default")
      (node (ref "J4") (pin "3") (pinfunction "3_3") (pintype "passive"))
      (node (ref "K4") (pin "1") (pinfunction "NC_1") (pintype "passive"))
    )
    (net (code "43") (name "/R3_NO") (class "Default")
      (node (ref "J4") (pin "1") (pinfunction "1_1") (pintype "passive"))
      (node (ref "K4") (pin "5") (pinfunction "NO_5") (pintype "passive"))
    )
    (net (code "44") (name "/R4_C") (class "Default")
      (node (ref "D3") (pin "2") (pinfunction "A_2") (pintype "passive"))
      (node (ref "K3") (pin "4") (pinfunction "C_2_4") (pintype "passive"))
      (node (ref "Q7") (pin "3") (pinfunction "C_3") (pintype "passive"))
    )
    (net (code "45") (name "/R4_COM") (class "Default")
      (node (ref "J3") (pin "2") (pinfunction "2_2") (pintype "passive"))
      (node (ref "K3") (pin "3") (pinfunction "COM_3") (pintype "passive"))
    )
    (net (code "46") (name "/R4_NC") (class "Default")
      (node (ref "J3") (pin "3") (pinfunction "3_3") (pintype "passive"))
      (node (ref "K3") (pin "1") (pinfunction "NC_1") (pintype "passive"))
    )
    (net (code "47") (name "/R4_NO") (class "Default")
      (node (ref "J3") (pin "1") (pinfunction "1_1") (pintype "passive"))
      (node (ref "K3") (pin "5") (pinfunction "NO_5") (pintype "passive"))
    )
    (net (code "48") (name "/R5_C") (class "Default")
      (node (ref "D6") (pin "2") (pinfunction "A_2") (pintype "passive"))
      (node (ref "K5") (pin "4") (pinfunction "C_2_4") (pintype "passive"))
      (node (ref "Q11") (pin "3") (pinfunction "C_3") (pintype "passive"))
    )
    (net (code "49") (name "/R5_COM") (class "Default")
      (node (ref "J6") (pin "2") (pinfunction "2_2") (pintype "passive"))
      (node (ref "K5") (pin "3") (pinfunction "COM_3") (pintype "passive"))
    )
    (net (code "50") (name "/R5_NC") (class "Default")
      (node (ref "J6") (pin "3") (pinfunction "3_3") (pintype "passive"))
      (node (ref "K5") (pin "1") (pinfunction "NC_1") (pintype "passive"))
    )
    (net (code "51") (name "/R5_NO") (class "Default")
      (node (ref "J6") (pin "1") (pinfunction "1_1") (pintype "passive"))
      (node (ref "K5") (pin "5") (pinfunction "NO_5") (pintype "passive"))
    )
    (net (code "52") (name "/R6_C") (class "Default")
      (node (ref "D7") (pin "2") (pinfunction "A_2") (pintype "passive"))
      (node (ref "K6") (pin "4") (pinfunction "C_2_4") (pintype "passive"))
      (node (ref "Q12") (pin "3") (pinfunction "C_3") (pintype "passive"))
    )
    (net (code "53") (name "/R6_COM") (class "Default")
      (node (ref "J7") (pin "2") (pinfunction "2_2") (pintype "passive"))
      (node (ref "K6") (pin "3") (pinfunction "COM_3") (pintype "passive"))
    )
    (net (code "54") (name "/R6_NC") (class "Default")
      (node (ref "J7") (pin "3") (pinfunction "3_3") (pintype "passive"))
      (node (ref "K6") (pin "1") (pinfunction "NC_1") (pintype "passive"))
    )
    (net (code "55") (name "/R6_NO") (class "Default")
      (node (ref "J7") (pin "1") (pinfunction "1_1") (pintype "passive"))
      (node (ref "K6") (pin "5") (pinfunction "NO_5") (pintype "passive"))
    )
    (net (code "56") (name "/RTS") (class "Default")
      (node (ref "P8") (pin "6") (pinfunction "6_6") (pintype "passive"))
      (node (ref "Q13") (pin "2") (pinfunction "E_2") (pintype "passive"))
      (node (ref "R16") (pin "2") (pinfunction "2_2") (pintype "passive"))
    )
    (net (code "57") (name "/RXD0") (class "Default")
      (node (ref "IC1") (pin "34") (pinfunction "RXD0_34") (pintype "passive"))
      (node (ref "P1") (pin "5") (pinfunction "5_5") (pintype "passive"))
      (node (ref "P8") (pin "3") (pinfunction "3_3") (pintype "passive"))
    )
    (net (code "58") (name "/SD0") (class "Default")
      (node (ref "IC1") (pin "21") (pinfunction "NC_5_21") (pintype "passive"))
      (node (ref "P1") (pin "18") (pinfunction "18_18") (pintype "passive"))
    )
    (net (code "59") (name "/SD1") (class "Default")
      (node (ref "IC1") (pin "22") (pinfunction "NC_6_22") (pintype "passive"))
      (node (ref "P1") (pin "17") (pinfunction "17_17") (pintype "passive"))
    )
    (net (code "60") (name "/SD2") (class "Default")
      (node (ref "IC1") (pin "17") (pinfunction "NC_1_17") (pintype "passive"))
      (node (ref "P2") (pin "16") (pinfunction "16_16") (pintype "passive"))
    )
    (net (code "61") (name "/SD3") (class "Default")
      (node (ref "IC1") (pin "18") (pinfunction "NC_2_18") (pintype "passive"))
      (node (ref "P2") (pin "17") (pinfunction "17_17") (pintype "passive"))
    )
    (net (code "62") (name "/SENSOR_VN") (class "Default")
      (node (ref "IC1") (pin "5") (pinfunction "SENSOR_VN_5") (pintype "passive"))
      (node (ref "P2") (pin "4") (pinfunction "4_4") (pintype "passive"))
    )
    (net (code "63") (name "/SENSOR_VP") (class "Default")
      (node (ref "IC1") (pin "4") (pinfunction "SENSOR_VP_4") (pintype "passive"))
      (node (ref "P2") (pin "3") (pinfunction "3_3") (pintype "passive"))
    )
    (net (code "64") (name "/TXD0") (class "Default")
      (node (ref "IC1") (pin "35") (pinfunction "TXD0_35") (pintype "passive"))
      (node (ref "P1") (pin "4") (pinfunction "4_4") (pintype "passive"))
      (node (ref "P8") (pin "4") (pinfunction "4_4") (pintype "passive"))
    )
    (net (code "65") (name "/VBAT") (class "Default")
      (node (ref "P5") (pin "7") (pinfunction "7_7") (pintype "passive+no_connect"))
    )
    (net (code "66") (name "GND") (class "Default")
      (node (ref "C1") (pin "2") (pinfunction "-_2") (pintype "passive"))
      (node (ref "C2") (pin "2") (pinfunction "-_2") (pintype "passive"))
      (node (ref "C3") (pin "1") (pinfunction "1_1") (pintype "passive"))
      (node (ref "C4") (pin "1") (pinfunction "1_1") (pintype "passive"))
      (node (ref "C5") (pin "2") (pinfunction "2_2") (pintype "passive"))
      (node (ref "C6") (pin "2") (pinfunction "2_2") (pintype "passive"))
      (node (ref "C7") (pin "2") (pinfunction "2_2") (pintype "passive"))
      (node (ref "D5") (pin "2") (pinfunction "A_2") (pintype "passive"))
      (node (ref "IC1") (pin "1") (pinfunction "GND_1_1") (pintype "passive"))
      (node (ref "IC1") (pin "15") (pinfunction "GND_2_15") (pintype "passive"))
      (node (ref "IC1") (pin "38") (pinfunction "GND_3_38") (pintype "passive"))
      (node (ref "IC1") (pin "39") (pinfunction "GND_4_39") (pintype "passive"))
      (node (ref "IC1") (pin "40") (pinfunction "GND_5_40") (pintype "passive"))
      (node (ref "IC1") (pin "41") (pinfunction "GND_6_41") (pintype "passive"))
      (node (ref "IC1") (pin "42") (pinfunction "GND_7_42") (pintype "passive"))
      (node (ref "IC1") (pin "43") (pinfunction "GND_8_43") (pintype "passive"))
      (node (ref "IC1") (pin "44") (pinfunction "GND_9_44") (pintype "passive"))
      (node (ref "IC1") (pin "45") (pinfunction "GND_10_45") (pintype "passive"))
      (node (ref "IC1") (pin "46") (pinfunction "GND_11_46") (pintype "passive"))
      (node (ref "IC1") (pin "47") (pinfunction "GND_12_47") (pintype "passive"))
      (node (ref "IC2") (pin "3") (pinfunction "GND_1_3") (pintype "passive"))
      (node (ref "IC2") (pin "5") (pinfunction "~{ON}/OFF_5") (pintype "passive"))
      (node (ref "IC3") (pin "1") (pinfunction "ADJ/GND_1") (pintype "passive"))
      (node (ref "J10") (pin "3") (pinfunction "3_3") (pintype "passive"))
      (node (ref "J5") (pin "1") (pinfunction "1_1") (pintype "passive"))
      (node (ref "J8") (pin "5") (pinfunction "5_5") (pintype "passive"))
      (node (ref "J9") (pin "3") (pinfunction "3_3") (pintype "passive"))
      (node (ref "P1") (pin "1") (pinfunction "1_1") (pintype "passive"))
      (node (ref "P1") (pin "7") (pinfunction "7_7") (pintype "passive"))
      (node (ref "P2") (pin "14") (pinfunction "14_14") (pintype "passive"))
      (node (ref "P3") (pin "2") (pinfunction "2_2") (pintype "passive"))
      (node (ref "P4") (pin "5") (pinfunction "5_5") (pintype "passive"))
      (node (ref "P5") (pin "6") (pinfunction "6_6") (pintype "passive"))
      (node (ref "P6") (pin "4") (pinfunction "4_4") (pintype "passive"))
      (node (ref "P7") (pin "5") (pinfunction "5_5") (pintype "passive"))
      (node (ref "P8") (pin "2") (pinfunction "2_2") (pintype "passive"))
      (node (ref "Q11") (pin "2") (pinfunction "E_2") (pintype "passive"))
      (node (ref "Q12") (pin "2") (pinfunction "E_2") (pintype "passive"))
      (node (ref "Q3") (pin "2") (pinfunction "E_2") (pintype "passive"))
      (node (ref "Q4") (pin "2") (pinfunction "E_2") (pintype "passive"))
      (node (ref "Q7") (pin "2") (pinfunction "E_2") (pintype "passive"))
      (node (ref "Q8") (pin "2") (pinfunction "E_2") (pintype "passive"))
      (node (ref "S1") (pin "1") (pinfunction "COM_1_1") (pintype "passive"))
      (node (ref "S1") (pin "2") (pinfunction "COM_2_2") (pintype "passive"))
      (node (ref "S2") (pin "1") (pinfunction "COM_1_1") (pintype "passive"))
      (node (ref "S2") (pin "2") (pinfunction "COM_2_2") (pintype "passive"))
    )
    (net (code "67") (name "Net-(D5-K)") (class "Default")
      (node (ref "D5") (pin "1") (pinfunction "K_1") (pintype "passive"))
      (node (ref "IC2") (pin "2") (pinfunction "O_2") (pintype "passive"))
      (node (ref "L1") (pin "1") (pinfunction "1_1") (pintype "passive"))
    )
    (net (code "68") (name "Net-(LED1-A)") (class "Default")
      (node (ref "LED1") (pin "2") (pinfunction "A_2") (pintype "passive"))
      (node (ref "Q1") (pin "2") (pinfunction "CATHODE_2") (pintype "passive"))
    )
    (net (code "69") (name "Net-(LED2-A)") (class "Default")
      (node (ref "LED2") (pin "2") (pinfunction "A_2") (pintype "passive"))
      (node (ref "Q2") (pin "2") (pinfunction "CATHODE_2") (pintype "passive"))
    )
    (net (code "70") (name "Net-(LED3-A)") (class "Default")
      (node (ref "LED3") (pin "2") (pinfunction "A_2") (pintype "passive"))
      (node (ref "Q5") (pin "2") (pinfunction "CATHODE_2") (pintype "passive"))
    )
    (net (code "71") (name "Net-(LED4-A)") (class "Default")
      (node (ref "LED4") (pin "2") (pinfunction "A_2") (pintype "passive"))
      (node (ref "Q6") (pin "2") (pinfunction "CATHODE_2") (pintype "passive"))
    )
    (net (code "72") (name "Net-(LED5-A)") (class "Default")
      (node (ref "LED5") (pin "2") (pinfunction "A_2") (pintype "passive"))
      (node (ref "Q9") (pin "2") (pinfunction "CATHODE_2") (pintype "passive"))
    )
    (net (code "73") (name "Net-(LED6-A)") (class "Default")
      (node (ref "LED6") (pin "2") (pinfunction "A_2") (pintype "passive"))
      (node (ref "Q10") (pin "2") (pinfunction "CATHODE_2") (pintype "passive"))
    )
    (net (code "74") (name "Net-(Q1-ANODE)") (class "Default")
      (node (ref "Q1") (pin "1") (pinfunction "ANODE_1") (pintype "passive"))
      (node (ref "R1") (pin "1") (pinfunction "1_1") (pintype "power_in"))
    )
    (net (code "75") (name "Net-(Q1-EMITTER)") (class "Default")
      (node (ref "Q1") (pin "3") (pinfunction "EMITTER_3") (pintype "passive"))
      (node (ref "R3") (pin "2") (pinfunction "2_2") (pintype "passive"))
    )
    (net (code "76") (name "Net-(Q2-ANODE)") (class "Default")
      (node (ref "Q2") (pin "1") (pinfunction "ANODE_1") (pintype "passive"))
      (node (ref "R2") (pin "1") (pinfunction "1_1") (pintype "power_in"))
    )
    (net (code "77") (name "Net-(Q2-EMITTER)") (class "Default")
      (node (ref "Q2") (pin "3") (pinfunction "EMITTER_3") (pintype "passive"))
      (node (ref "R4") (pin "2") (pinfunction "2_2") (pintype "passive"))
    )
    (net (code "78") (name "Net-(Q3-B)") (class "Default")
      (node (ref "Q3") (pin "1") (pinfunction "B_1") (pintype "passive"))
      (node (ref "R3") (pin "1") (pinfunction "1_1") (pintype "passive"))
    )
    (net (code "79") (name "Net-(Q4-B)") (class "Default")
      (node (ref "Q4") (pin "1") (pinfunction "B_1") (pintype "passive"))
      (node (ref "R4") (pin "1") (pinfunction "1_1") (pintype "passive"))
    )
    (net (code "80") (name "Net-(Q5-ANODE)") (class "Default")
      (node (ref "Q5") (pin "1") (pinfunction "ANODE_1") (pintype "passive"))
      (node (ref "R5") (pin "1") (pinfunction "1_1") (pintype "power_in"))
    )
    (net (code "81") (name "Net-(Q5-EMITTER)") (class "Default")
      (node (ref "Q5") (pin "3") (pinfunction "EMITTER_3") (pintype "passive"))
      (node (ref "R7") (pin "2") (pinfunction "2_2") (pintype "passive"))
    )
    (net (code "82") (name "Net-(Q6-ANODE)") (class "Default")
      (node (ref "Q6") (pin "1") (pinfunction "ANODE_1") (pintype "passive"))
      (node (ref "R6") (pin "1") (pinfunction "1_1") (pintype "power_in"))
    )
    (net (code "83") (name "Net-(Q6-EMITTER)") (class "Default")
      (node (ref "Q6") (pin "3") (pinfunction "EMITTER_3") (pintype "passive"))
      (node (ref "R8") (pin "2") (pinfunction "2_2") (pintype "passive"))
    )
    (net (code "84") (name "Net-(Q7-B)") (class "Default")
      (node (ref "Q7") (pin "1") (pinfunction "B_1") (pintype "passive"))
      (node (ref "R7") (pin "1") (pinfunction "1_1") (pintype "passive"))
    )
    (net (code "85") (name "Net-(Q8-B)") (class "Default")
      (node (ref "Q8") (pin "1") (pinfunction "B_1") (pintype "passive"))
      (node (ref "R8") (pin "1") (pinfunction "1_1") (pintype "passive"))
    )
    (net (code "86") (name "Net-(Q9-ANODE)") (class "Default")
      (node (ref "Q9") (pin "1") (pinfunction "ANODE_1") (pintype "passive"))
      (node (ref "R9") (pin "1") (pinfunction "1_1") (pintype "power_in"))
    )
    (net (code "87") (name "Net-(Q9-EMITTER)") (class "Default")
      (node (ref "Q9") (pin "3") (pinfunction "EMITTER_3") (pintype "passive"))
      (node (ref "R11") (pin "2") (pinfunction "2_2") (pintype "passive"))
    )
    (net (code "88") (name "Net-(Q10-ANODE)") (class "Default")
      (node (ref "Q10") (pin "1") (pinfunction "ANODE_1") (pintype "passive"))
      (node (ref "R10") (pin "1") (pinfunction "1_1") (pintype "power_in"))
    )
    (net (code "89") (name "Net-(Q10-EMITTER)") (class "Default")
      (node (ref "Q10") (pin "3") (pinfunction "EMITTER_3") (pintype "passive"))
      (node (ref "R12") (pin "2") (pinfunction "2_2") (pintype "passive"))
    )
    (net (code "90") (name "Net-(Q11-B)") (class "Default")
      (node (ref "Q11") (pin "1") (pinfunction "B_1") (pintype "passive"))
      (node (ref "R11") (pin "1") (pinfunction "1_1") (pintype "passive"))
    )
    (net (code "91") (name "Net-(Q12-B)") (class "Default")
      (node (ref "Q12") (pin "1") (pinfunction "B_1") (pintype "passive"))
      (node (ref "R12") (pin "1") (pinfunction "1_1") (pintype "passive"))
    )
    (net (code "92") (name "Net-(Q13-B)") (class "Default")
      (node (ref "Q13") (pin "1") (pinfunction "B_1") (pintype "passive"))
      (node (ref "R15") (pin "1") (pinfunction "1_1") (pintype "passive"))
    )
    (net (code "93") (name "Net-(Q14-B)") (class "Default")
      (node (ref "Q14") (pin "1") (pinfunction "B_1") (pintype "passive"))
      (node (ref "R16") (pin "1") (pinfunction "1_1") (pintype "passive"))
    )
    (net (code "94") (name "VCC_3.3V") (class "Default")
      (node (ref "C4") (pin "2") (pinfunction "2_2") (pintype "passive"))
      (node (ref "IC1") (pin "2") (pinfunction "3V3_2") (pintype "passive"))
      (node (ref "IC3") (pin "2") (pinfunction "OUTPUT_2") (pintype "passive"))
      (node (ref "IC3") (pin "4") (pinfunction "VOUT_4") (pintype "passive"))
      (node (ref "J10") (pin "1") (pinfunction "1_1") (pintype "passive"))
      (node (ref "J9") (pin "1") (pinfunction "1_1") (pintype "passive"))
      (node (ref "P2") (pin "1") (pinfunction "1_1") (pintype "passive"))
      (node (ref "P3") (pin "1") (pinfunction "1_1") (pintype "passive"))
      (node (ref "P4") (pin "1") (pinfunction "1_1") (pintype "passive"))
      (node (ref "P5") (pin "5") (pinfunction "5_5") (pintype "passive"))
      (node (ref "P6") (pin "1") (pinfunction "1_1") (pintype "passive"))
      (node (ref "P7") (pin "4") (pinfunction "4_4") (pintype "passive"))
      (node (ref "P8") (pin "1") (pinfunction "1_1") (pintype "passive"))
      (node (ref "R13") (pin "2") (pinfunction "2_2") (pintype "passive"))
      (node (ref "R14") (pin "2") (pinfunction "2_2") (pintype "passive"))
    )
    (net (code "95") (name "VCC_5V") (class "Default")
      (node (ref "C2") (pin "1") (pinfunction "+_1") (pintype "passive"))
      (node (ref "C3") (pin "2") (pinfunction "2_2") (pintype "passive"))
      (node (ref "D1") (pin "1") (pinfunction "K_1") (pintype "passive"))
      (node (ref "D2") (pin "1") (pinfunction "K_1") (pintype "passive"))
      (node (ref "D3") (pin "1") (pinfunction "K_1") (pintype "passive"))
      (node (ref "D4") (pin "1") (pinfunction "K_1") (pintype "passive"))
      (node (ref "D6") (pin "1") (pinfunction "K_1") (pintype "passive"))
      (node (ref "D7") (pin "1") (pinfunction "K_1") (pintype "passive"))
      (node (ref "IC2") (pin "4") (pinfunction "FB_4") (pintype "passive"))
      (node (ref "IC3") (pin "3") (pinfunction "INPUT_3") (pintype "passive"))
      (node (ref "K1") (pin "2") (pinfunction "C_1_2") (pintype "passive"))
      (node (ref "K2") (pin "2") (pinfunction "C_1_2") (pintype "passive"))
      (node (ref "K3") (pin "2") (pinfunction "C_1_2") (pintype "passive"))
      (node (ref "K4") (pin "2") (pinfunction "C_1_2") (pintype "passive"))
      (node (ref "K5") (pin "2") (pinfunction "C_1_2") (pintype "passive"))
      (node (ref "K6") (pin "2") (pinfunction "C_1_2") (pintype "passive"))
      (node (ref "L1") (pin "2") (pinfunction "2_2") (pintype "passive"))
      (node (ref "P2") (pin "19") (pinfunction "19_19") (pintype "passive"))
      (node (ref "Q1") (pin "4") (pinfunction "COLLECTOR_4") (pintype "passive"))
      (node (ref "Q10") (pin "4") (pinfunction "COLLECTOR_4") (pintype "passive"))
      (node (ref "Q2") (pin "4") (pinfunction "COLLECTOR_4") (pintype "passive"))
      (node (ref "Q5") (pin "4") (pinfunction "COLLECTOR_4") (pintype "passive"))
      (node (ref "Q6") (pin "4") (pinfunction "COLLECTOR_4") (pintype "passive"))
      (node (ref "Q9") (pin "4") (pinfunction "COLLECTOR_4") (pintype "passive"))
      (node (ref "R1") (pin "2") (pinfunction "2_2") (pintype "power_in"))
      (node (ref "R10") (pin "2") (pinfunction "2_2") (pintype "power_in"))
      (node (ref "R2") (pin "2") (pinfunction "2_2") (pintype "power_in"))
      (node (ref "R5") (pin "2") (pinfunction "2_2") (pintype "power_in"))
      (node (ref "R6") (pin "2") (pinfunction "2_2") (pintype "power_in"))
      (node (ref "R9") (pin "2") (pinfunction "2_2") (pintype "power_in"))
    )
    (net (code "96") (name "VIN") (class "Default")
      (node (ref "C1") (pin "1") (pinfunction "+_1") (pintype "passive"))
      (node (ref "IC2") (pin "1") (pinfunction "VIN_1") (pintype "passive"))
      (node (ref "J5") (pin "2") (pinfunction "2_2") (pintype "passive"))
    )
    (net (code "97") (name "unconnected-(P3-Pad5)") (class "Default")
      (node (ref "P3") (pin "5") (pinfunction "5_5") (pintype "passive+no_connect"))
    )
    (net (code "98") (name "unconnected-(P3-Pad6)") (class "Default")
      (node (ref "P3") (pin "6") (pinfunction "6_6") (pintype "passive+no_connect"))
    )
    (net (code "99") (name "unconnected-(P5-Pad1)") (class "Default")
      (node (ref "P5") (pin "1") (pinfunction "1_1") (pintype "passive+no_connect"))
    )
    (net (code "100") (name "unconnected-(P5-Pad2)") (class "Default")
      (node (ref "P5") (pin "2") (pinfunction "2_2") (pintype "passive+no_connect"))
    )
    (net (code "101") (name "unconnected-(P7-Pad1)") (class "Default")
      (node (ref "P7") (pin "1") (pinfunction "1_1") (pintype "passive+no_connect"))
    )
  )
)
